# RF.net
KiCad netlist of a schematic drawn in Altium Designer
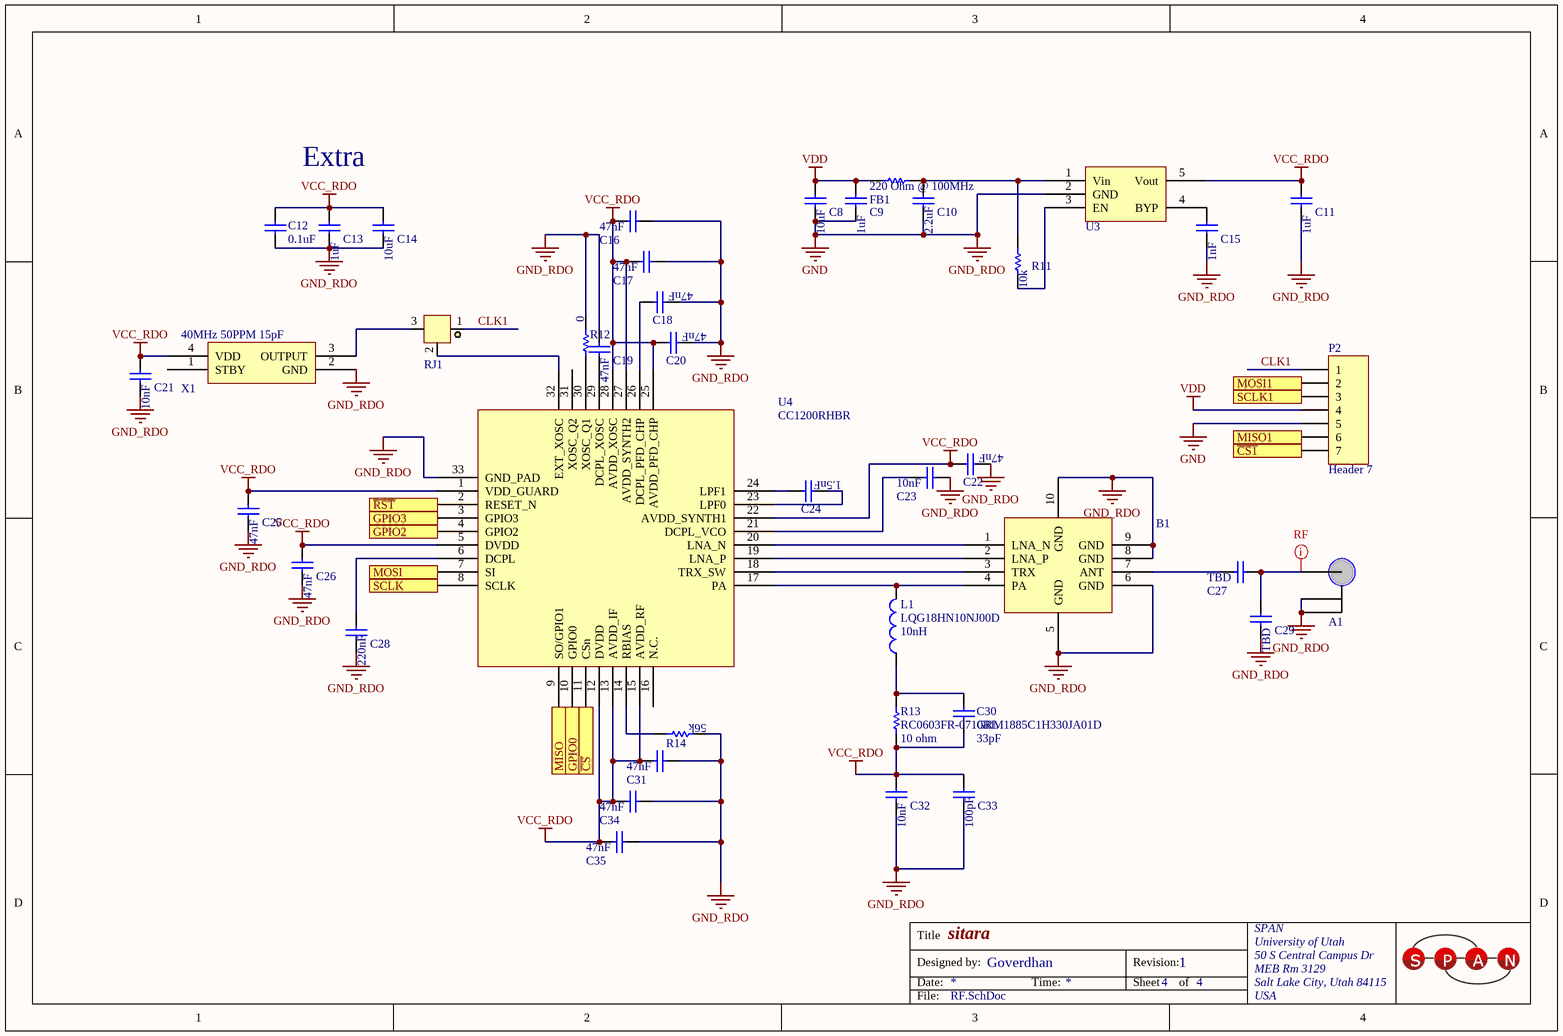
[diagram p0: RF.SchDoc]

(export (version "E")
  (design (tool "Eeschema 10.0.6"))
  (components
    (comp (ref "A1")
      (value "U.FL-R-SMT(01)")
      (footprint "U.FL-R-SMT-1")
      (description "CONN UMC JACK STR 50 OHM SMD")
      (fields (field (name "MANUFACTURER") "Hirose Electric Co Ltd"))
      (libsource (lib "Sara") (part "U.FL-R-SMT(01)"))
    )
    (comp (ref "B1")
      (value "0900PC15J0013")
      (footprint "0900PC15J0013")
      (description "TI CC1120 1121 BALUN FILTER IPC")
      (fields (field (name "MANUFACTURER") "Johanson Technology Inc."))
      (libsource (lib "Sara") (part "0900PC15J0013"))
    )
    (comp (ref "C8")
      (value "GRM188R60J106ME47D")
      (footprint "CAPC1608X08N (0603)")
      (description "CAP CER 10UF 6.3V 20% X5R 0603")
      (fields
        (field (name "MANUFACTURER") "Murata Electronics North America")
        (field (name "TOLERANCE") "±20%")
      )
      (libsource (lib "Sara") (part "GRM188R60J106ME47D"))
    )
    (comp (ref "C9")
      (value "GRM188R61A105KA61D")
      (footprint "CAPC1608X08N (0603)")
      (description "CAP CER 1UF 10V 10% X5R 0603")
      (fields
        (field (name "MANUFACTURER") "Murata Electronics North America")
        (field (name "TOLERANCE") "±10%")
      )
      (libsource (lib "Sara") (part "GRM188R61A105KA61D"))
    )
    (comp (ref "C10")
      (value "GRM188F51A225ZE01D")
      (footprint "CAPC1608X08N (0603)")
      (description "CAP CER 2.2UF 10V Y5V 0603")
      (fields
        (field (name "MANUFACTURER") "Murata Electronics North America")
        (field (name "TOLERANCE") "-20%, +80%")
      )
      (libsource (lib "Sara") (part "GRM188F51A225ZE01D"))
    )
    (comp (ref "C11")
      (value "GRM188R61A105KA61D")
      (footprint "CAPC1608X08N (0603)")
      (description "CAP CER 1UF 10V 10% X5R 0603")
      (fields
        (field (name "MANUFACTURER") "Murata Electronics North America")
        (field (name "TOLERANCE") "±10%")
      )
      (libsource (lib "Sara") (part "GRM188R61A105KA61D"))
    )
    (comp (ref "C12")
      (value "0.1uF")
      (footprint "0603_Cap")
      (description "CAP CER 0.1UF 16V X7R 0603")
      (fields
        (field (name "MANUFACTURER") "AVX Corporation")
        (field (name "MANUFACTURER PART NUMBER") "0603YC104KAT4A")
      )
      (libsource (lib "Sitara") (part "0603YC104KAT4A"))
    )
    (comp (ref "C13")
      (value "GRM188R61A105KA61D")
      (footprint "CAPC1608X08N (0603)")
      (description "CAP CER 1UF 10V 10% X5R 0603")
      (fields
        (field (name "MANUFACTURER") "Murata Electronics North America")
        (field (name "TOLERANCE") "±10%")
      )
      (libsource (lib "Sara") (part "GRM188R61A105KA61D"))
    )
    (comp (ref "C14")
      (value "GRM188R60J106ME47D")
      (footprint "CAPC1608X08N (0603)")
      (description "CAP CER 10UF 6.3V 20% X5R 0603")
      (fields
        (field (name "MANUFACTURER") "Murata Electronics North America")
        (field (name "TOLERANCE") "±20%")
      )
      (libsource (lib "Sara") (part "GRM188R60J106ME47D"))
    )
    (comp (ref "C15")
      (value "GRM1885C1H102JA01D")
      (footprint "CAPC1608X08N (0603)")
      (description "CAP CER 1000PF 50V 5% NP0 0603")
      (fields
        (field (name "MANUFACTURER") "Murata Electronics North America")
        (field (name "TOLERANCE") "±5%")
      )
      (libsource (lib "Sara") (part "GRM1885C1H102JA01D"))
    )
    (comp (ref "C16")
      (value "GCM188R71H473KA55D")
      (footprint "CAPC1608X08N (0603)")
      (description "CAP CER 0.047UF 50V 10% X7R 0603")
      (fields
        (field (name "MANUFACTURER") "Murata Electronics North America")
        (field (name "TOLERANCE") "±10%")
      )
      (libsource (lib "Sara") (part "GCM188R71H473KA55D"))
    )
    (comp (ref "C17")
      (value "GCM188R71H473KA55D")
      (footprint "CAPC1608X08N (0603)")
      (description "CAP CER 0.047UF 50V 10% X7R 0603")
      (fields
        (field (name "MANUFACTURER") "Murata Electronics North America")
        (field (name "TOLERANCE") "±10%")
      )
      (libsource (lib "Sara") (part "GCM188R71H473KA55D"))
    )
    (comp (ref "C18")
      (value "GCM188R71H473KA55D")
      (footprint "CAPC1608X08N (0603)")
      (description "CAP CER 0.047UF 50V 10% X7R 0603")
      (fields
        (field (name "MANUFACTURER") "Murata Electronics North America")
        (field (name "TOLERANCE") "±10%")
      )
      (libsource (lib "Sara") (part "GCM188R71H473KA55D"))
    )
    (comp (ref "C19")
      (value "GCM188R71H473KA55D")
      (footprint "CAPC1608X08N (0603)")
      (description "CAP CER 0.047UF 50V 10% X7R 0603")
      (fields
        (field (name "MANUFACTURER") "Murata Electronics North America")
        (field (name "TOLERANCE") "±10%")
      )
      (libsource (lib "Sara") (part "GCM188R71H473KA55D"))
    )
    (comp (ref "C20")
      (value "GCM188R71H473KA55D")
      (footprint "CAPC1608X08N (0603)")
      (description "CAP CER 0.047UF 50V 10% X7R 0603")
      (fields
        (field (name "MANUFACTURER") "Murata Electronics North America")
        (field (name "TOLERANCE") "±10%")
      )
      (libsource (lib "Sara") (part "GCM188R71H473KA55D"))
    )
    (comp (ref "C21")
      (value "GRM188R71H103MA01D")
      (footprint "CAPC1608X08N (0603)")
      (description "CAP CER 10000PF 50V 20% X7R 0603")
      (fields
        (field (name "MANUFACTURER") "Murata Electronics North America")
        (field (name "TOLERANCE") "±20%")
      )
      (libsource (lib "Sara") (part "GRM188R71H103MA01D"))
    )
    (comp (ref "C22")
      (value "GCM188R71H473KA55D")
      (footprint "CAPC1608X08N (0603)")
      (description "CAP CER 0.047UF 50V 10% X7R 0603")
      (fields
        (field (name "MANUFACTURER") "Murata Electronics North America")
        (field (name "TOLERANCE") "±10%")
      )
      (libsource (lib "Sara") (part "GCM188R71H473KA55D"))
    )
    (comp (ref "C23")
      (value "GRM188R71H103MA01D")
      (footprint "CAPC1608X08N (0603)")
      (description "CAP CER 10000PF 50V 20% X7R 0603")
      (fields
        (field (name "MANUFACTURER") "Murata Electronics North America")
        (field (name "TOLERANCE") "±20%")
      )
      (libsource (lib "Sara") (part "GRM188R71H103MA01D"))
    )
    (comp (ref "C24")
      (value "GRM1885C1H152JA01D")
      (footprint "CAPC1608X08N (0603)")
      (description "CAP CER 1500PF 50V 5% NP0 0603")
      (fields
        (field (name "MANUFACTURER") "Murata Electronics North America")
        (field (name "TOLERANCE") "±5%")
      )
      (libsource (lib "Sara") (part "GRM1885C1H152JA01D"))
    )
    (comp (ref "C25")
      (value "GCM188R71H473KA55D")
      (footprint "CAPC1608X08N (0603)")
      (description "CAP CER 0.047UF 50V 10% X7R 0603")
      (fields
        (field (name "MANUFACTURER") "Murata Electronics North America")
        (field (name "TOLERANCE") "±10%")
      )
      (libsource (lib "Sara") (part "GCM188R71H473KA55D"))
    )
    (comp (ref "C26")
      (value "GCM188R71H473KA55D")
      (footprint "CAPC1608X08N (0603)")
      (description "CAP CER 0.047UF 50V 10% X7R 0603")
      (fields
        (field (name "MANUFACTURER") "Murata Electronics North America")
        (field (name "TOLERANCE") "±10%")
      )
      (libsource (lib "Sara") (part "GCM188R71H473KA55D"))
    )
    (comp (ref "C27")
      (value "C_TBD")
      (footprint "CAPC1608X08N (0603)")
      (libsource (lib "Sara") (part "C_TBD"))
    )
    (comp (ref "C28")
      (value "GRM188R71E224KA88D")
      (footprint "CAPC1608X08N (0603)")
      (description "CAP CER 0.22UF 25V 10% X7R 0603")
      (fields
        (field (name "MANUFACTURER") "Murata Electronics North America")
        (field (name "TOLERANCE") "±10%")
      )
      (libsource (lib "Sara") (part "GRM188R71E224KA88D"))
    )
    (comp (ref "C29")
      (value "C_TBD")
      (footprint "CAPC1608X08N (0603)")
      (libsource (lib "Sara") (part "C_TBD"))
    )
    (comp (ref "C30")
      (value "GRM1885C1H330JA01D")
      (footprint "CAPC1608X08N (0603)")
      (description "CAP CER 33PF 50V NP0 0603")
      (fields
        (field (name "MANUFACTURER") "Murata Electronics North America")
        (field (name "TOLERANCE") "±5%")
        (field (name "ALTIUM_VALUE") "33pF")
      )
      (libsource (lib "Sara") (part "GRM1885C1H330JA01D"))
    )
    (comp (ref "C31")
      (value "GCM188R71H473KA55D")
      (footprint "CAPC1608X08N (0603)")
      (description "CAP CER 0.047UF 50V 10% X7R 0603")
      (fields
        (field (name "MANUFACTURER") "Murata Electronics North America")
        (field (name "TOLERANCE") "±10%")
      )
      (libsource (lib "Sara") (part "GCM188R71H473KA55D"))
    )
    (comp (ref "C32")
      (value "GRM188R71H103MA01D")
      (footprint "CAPC1608X08N (0603)")
      (description "CAP CER 10000PF 50V 20% X7R 0603")
      (fields
        (field (name "MANUFACTURER") "Murata Electronics North America")
        (field (name "TOLERANCE") "±20%")
      )
      (libsource (lib "Sara") (part "GRM188R71H103MA01D"))
    )
    (comp (ref "C33")
      (value "GQM1885C1H101JB01D")
      (footprint "CAPC1608X08N (0603)")
      (description "CAP CER 100PF 50V 5% NP0 0603")
      (fields
        (field (name "MANUFACTURER") "Murata Electronics North America")
        (field (name "TOLERANCE") "±5%")
      )
      (libsource (lib "Sara") (part "GQM1885C1H101JB01D"))
    )
    (comp (ref "C34")
      (value "GCM188R71H473KA55D")
      (footprint "CAPC1608X08N (0603)")
      (description "CAP CER 0.047UF 50V 10% X7R 0603")
      (fields
        (field (name "MANUFACTURER") "Murata Electronics North America")
        (field (name "TOLERANCE") "±10%")
      )
      (libsource (lib "Sara") (part "GCM188R71H473KA55D"))
    )
    (comp (ref "C35")
      (value "GCM188R71H473KA55D")
      (footprint "CAPC1608X08N (0603)")
      (description "CAP CER 0.047UF 50V 10% X7R 0603")
      (fields
        (field (name "MANUFACTURER") "Murata Electronics North America")
        (field (name "TOLERANCE") "±10%")
      )
      (libsource (lib "Sara") (part "GCM188R71H473KA55D"))
    )
    (comp (ref "FB1")
      (value "BLM18BD221SN1D")
      (footprint "RESC1608X06N (0603)")
      (description "FERRITE CHIP 220 OHM 200MA 0603")
      (fields (field (name "MANUFACTURER") "Murata Electronics North America"))
      (libsource (lib "Sara") (part "BLM18BD221SN1D"))
    )
    (comp (ref "L1")
      (value "LQG18HN10NJ00D")
      (footprint "INDC1608X08N")
      (description "FIXED IND 10NH 400MA 300 MOHM")
      (fields
        (field (name "MANUFACTURER") "Murata Electronics North America")
        (field (name "TOLERANCE") "±5%")
        (field (name "ALTIUM_VALUE") "10nH")
      )
      (libsource (lib "Sara") (part "LQG18HN10NJ00D"))
    )
    (comp (ref "P2")
      (value "Header 7")
      (footprint "HDR1X7")
      (description "Header, 7-Pin")
      (fields (field (name "PUBLISHER") "Altium Limited"))
      (libsource (lib "Cerberus") (part "Header 7"))
    )
    (comp (ref "R11")
      (value "RC0603FR-0710KL")
      (footprint "RESC1608X06N (0603)")
      (description "RES 10.0K OHM 1/10W 1% 0603 SMD")
      (fields (field (name "MANUFACTURER") "Yageo") (field (name "TOLERANCE") "±1%"))
      (libsource (lib "Sara") (part "RC0603FR-0710KL"))
    )
    (comp (ref "R12")
      (value "MCR03ERTJ000")
      (footprint "RESC1608X06N (0603)")
      (description "RES 0.0 OHM 1/10W JUMP 0603 SMD")
      (fields (field (name "MANUFACTURER") "Rohm Semiconductor") (field (name "TOLERANCE") "Jumper"))
      (libsource (lib "Sara") (part "MCR03ERTJ000"))
    )
    (comp (ref "R13")
      (value "RC0603FR-0710RL")
      (footprint "RESC1608X06N (0603)")
      (description "RES SMD 10 OHM 1% 1/10W 0603")
      (fields
        (field (name "MANUFACTURER") "Yageo")
        (field (name "TOLERANCE") "±1%")
        (field (name "ALTIUM_VALUE") "10 ohm")
      )
      (libsource (lib "Sara") (part "RC0603FR-0710RL"))
    )
    (comp (ref "R14")
      (value "MCR03ERTJ563")
      (footprint "RESC1608X06N (0603)")
      (description "RES 56K OHM 1/10W 5% 0603 SMD")
      (fields (field (name "MANUFACTURER") "Rohm Semiconductor") (field (name "TOLERANCE") "±5%"))
      (libsource (lib "Sara") (part "MCR03ERTJ563"))
    )
    (comp (ref "RJ1")
      (value "R_J")
      (footprint "RJ")
      (description "Resistor Jumper")
      (libsource (lib "Chronos") (part "R_J"))
    )
    (comp (ref "U3")
      (value "FAN2500S30X")
      (footprint "SOT95P280X145-5N")
      (description "IC REG LDO 3V 0.1A SOT23-5")
      (fields (field (name "MANUFACTURER") "Fairchild Semiconductor"))
      (libsource (lib "Sara") (part "FAN2500S30X"))
    )
    (comp (ref "U4")
      (value "CC1200RHBR")
      (footprint "S-PVQFN-N32")
      (description "IC RF TXRX SNGL-CHIP LP 32-QFN")
      (fields (field (name "MANUFACTURER") "Texas Instruments"))
      (libsource (lib "Sara") (part "CC1200RHBR"))
    )
    (comp (ref "X1")
      (value "ASE-40.000MHZ-L-C-T")
      (footprint "3.2x2.5x1.2mmXTAL")
      (description "OSC XO 40.0000MHZ LVCMOS SMD")
      (fields (field (name "MANUFACTURER") "Abracon LLC"))
      (libsource (lib "Sara") (part "ASE-40.000MHZ-L-C-T"))
    )
  )
  (nets
    (net (code "1") (name "/CLK1") (class "Default")
      (node (ref "P2") (pin "1") (pinfunction "1_1") (pintype "passive"))
      (node (ref "RJ1") (pin "1") (pinfunction "1_1") (pintype "passive"))
    )
    (net (code "2") (name "/GPIO0") (class "Default")
      (node (ref "U4") (pin "10") (pinfunction "GPIO0_10") (pintype "passive"))
    )
    (net (code "3") (name "/GPIO2") (class "Default")
      (node (ref "U4") (pin "4") (pinfunction "GPIO2_4") (pintype "passive"))
    )
    (net (code "4") (name "/GPIO3") (class "Default")
      (node (ref "U4") (pin "3") (pinfunction "GPIO3_3") (pintype "passive"))
    )
    (net (code "5") (name "/MISO") (class "Default")
      (node (ref "U4") (pin "9") (pinfunction "SO/GPIO1_9") (pintype "passive"))
    )
    (net (code "6") (name "/MISO1") (class "Default")
      (node (ref "P2") (pin "6") (pinfunction "6_6") (pintype "passive"))
    )
    (net (code "7") (name "/MOSI") (class "Default")
      (node (ref "U4") (pin "7") (pinfunction "SI_7") (pintype "passive"))
    )
    (net (code "8") (name "/MOSI1") (class "Default")
      (node (ref "P2") (pin "2") (pinfunction "2_2") (pintype "passive"))
    )
    (net (code "9") (name "/SCLK") (class "Default")
      (node (ref "U4") (pin "8") (pinfunction "SCLK_8") (pintype "passive"))
    )
    (net (code "10") (name "/SCLK1") (class "Default")
      (node (ref "P2") (pin "3") (pinfunction "3_3") (pintype "passive"))
    )
    (net (code "11") (name "/~{CS1}") (class "Default")
      (node (ref "P2") (pin "7") (pinfunction "7_7") (pintype "passive"))
    )
    (net (code "12") (name "/~{CS}") (class "Default")
      (node (ref "U4") (pin "11") (pinfunction "CSn_11") (pintype "passive"))
    )
    (net (code "13") (name "/~{RST}") (class "Default")
      (node (ref "U4") (pin "2") (pinfunction "RESET_N_2") (pintype "passive"))
    )
    (net (code "14") (name "GND") (class "Default")
      (node (ref "A1") (pin "2") (pinfunction "2_2") (pintype "passive"))
      (node (ref "A1") (pin "3") (pinfunction "3_3") (pintype "passive"))
      (node (ref "B1") (pin "10") (pinfunction "GND_10") (pintype "passive"))
      (node (ref "B1") (pin "5") (pinfunction "GND_5") (pintype "passive"))
      (node (ref "B1") (pin "6") (pinfunction "GND_6") (pintype "passive"))
      (node (ref "B1") (pin "8") (pinfunction "GND_8") (pintype "passive"))
      (node (ref "B1") (pin "9") (pinfunction "GND_9") (pintype "passive"))
      (node (ref "C10") (pin "1") (pinfunction "1_1") (pintype "passive"))
      (node (ref "C11") (pin "1") (pinfunction "1_1") (pintype "passive"))
      (node (ref "C12") (pin "1") (pinfunction "1_1") (pintype "passive"))
      (node (ref "C13") (pin "1") (pinfunction "1_1") (pintype "passive"))
      (node (ref "C14") (pin "1") (pinfunction "1_1") (pintype "passive"))
      (node (ref "C15") (pin "1") (pinfunction "1_1") (pintype "passive"))
      (node (ref "C16") (pin "2") (pinfunction "2_2") (pintype "passive"))
      (node (ref "C17") (pin "2") (pinfunction "2_2") (pintype "passive"))
      (node (ref "C18") (pin "1") (pinfunction "1_1") (pintype "passive"))
      (node (ref "C19") (pin "2") (pinfunction "2_2") (pintype "passive"))
      (node (ref "C20") (pin "1") (pinfunction "1_1") (pintype "passive"))
      (node (ref "C21") (pin "1") (pinfunction "1_1") (pintype "passive"))
      (node (ref "C22") (pin "1") (pinfunction "1_1") (pintype "passive"))
      (node (ref "C23") (pin "2") (pinfunction "2_2") (pintype "passive"))
      (node (ref "C25") (pin "1") (pinfunction "1_1") (pintype "passive"))
      (node (ref "C26") (pin "1") (pinfunction "1_1") (pintype "passive"))
      (node (ref "C28") (pin "1") (pinfunction "1_1") (pintype "passive"))
      (node (ref "C29") (pin "1") (pinfunction "1_1") (pintype "passive"))
      (node (ref "C31") (pin "2") (pinfunction "2_2") (pintype "passive"))
      (node (ref "C32") (pin "1") (pinfunction "1_1") (pintype "passive"))
      (node (ref "C33") (pin "1") (pinfunction "1_1") (pintype "passive"))
      (node (ref "C34") (pin "2") (pinfunction "2_2") (pintype "passive"))
      (node (ref "C35") (pin "2") (pinfunction "2_2") (pintype "passive"))
      (node (ref "C8") (pin "1") (pinfunction "1_1") (pintype "passive"))
      (node (ref "C9") (pin "1") (pinfunction "1_1") (pintype "passive"))
      (node (ref "P2") (pin "5") (pinfunction "5_5") (pintype "passive"))
      (node (ref "R12") (pin "1") (pinfunction "1_1") (pintype "passive"))
      (node (ref "R14") (pin "1") (pinfunction "1_1") (pintype "passive"))
      (node (ref "U3") (pin "2") (pinfunction "GND_2") (pintype "passive"))
      (node (ref "U4") (pin "33") (pinfunction "GND_PAD_33") (pintype "passive"))
      (node (ref "X1") (pin "2") (pinfunction "GND_2") (pintype "passive"))
    )
    (net (code "15") (name "Net-(A1-Pad1)") (class "Default")
      (node (ref "A1") (pin "1") (pinfunction "1_1") (pintype "passive"))
      (node (ref "C27") (pin "2") (pinfunction "2_2") (pintype "passive"))
      (node (ref "C29") (pin "2") (pinfunction "2_2") (pintype "passive"))
    )
    (net (code "16") (name "Net-(B1-ANT)") (class "Default")
      (node (ref "B1") (pin "7") (pinfunction "ANT_7") (pintype "passive"))
      (node (ref "C27") (pin "1") (pinfunction "1_1") (pintype "passive"))
    )
    (net (code "17") (name "Net-(B1-LNA_N)") (class "Default")
      (node (ref "B1") (pin "1") (pinfunction "LNA_N_1") (pintype "passive"))
      (node (ref "U4") (pin "20") (pinfunction "LNA_N_20") (pintype "passive"))
    )
    (net (code "18") (name "Net-(B1-LNA_P)") (class "Default")
      (node (ref "B1") (pin "2") (pinfunction "LNA_P_2") (pintype "passive"))
      (node (ref "U4") (pin "19") (pinfunction "LNA_P_19") (pintype "passive"))
    )
    (net (code "19") (name "Net-(B1-PA)") (class "Default")
      (node (ref "B1") (pin "4") (pinfunction "PA_4") (pintype "passive"))
      (node (ref "L1") (pin "2") (pinfunction "2_2") (pintype "passive"))
      (node (ref "U4") (pin "17") (pinfunction "PA_17") (pintype "passive"))
    )
    (net (code "20") (name "Net-(B1-TRX)") (class "Default")
      (node (ref "B1") (pin "3") (pinfunction "TRX_3") (pintype "passive"))
      (node (ref "U4") (pin "18") (pinfunction "TRX_SW_18") (pintype "passive"))
    )
    (net (code "21") (name "Net-(C30-Pad2)") (class "Default")
      (node (ref "C30") (pin "2") (pinfunction "2_2") (pintype "passive"))
      (node (ref "L1") (pin "1") (pinfunction "1_1") (pintype "passive"))
      (node (ref "R13") (pin "2") (pinfunction "2_2") (pintype "passive"))
    )
    (net (code "22") (name "Net-(U3-BYP)") (class "Default")
      (node (ref "C15") (pin "2") (pinfunction "2_2") (pintype "passive"))
      (node (ref "U3") (pin "4") (pinfunction "BYP_4") (pintype "passive"))
    )
    (net (code "23") (name "Net-(U3-EN)") (class "Default")
      (node (ref "R11") (pin "1") (pinfunction "1_1") (pintype "passive"))
      (node (ref "U3") (pin "3") (pinfunction "EN_3") (pintype "passive"))
    )
    (net (code "24") (name "Net-(U3-Vin)") (class "Default")
      (node (ref "C10") (pin "2") (pinfunction "2_2") (pintype "passive"))
      (node (ref "FB1") (pin "2") (pinfunction "2_2") (pintype "passive"))
      (node (ref "R11") (pin "2") (pinfunction "2_2") (pintype "passive"))
      (node (ref "U3") (pin "1") (pinfunction "Vin_1") (pintype "passive"))
    )
    (net (code "25") (name "Net-(U4-DCPL)") (class "Default")
      (node (ref "C28") (pin "2") (pinfunction "2_2") (pintype "passive"))
      (node (ref "U4") (pin "6") (pinfunction "DCPL_6") (pintype "passive"))
    )
    (net (code "26") (name "Net-(U4-DCPL_PFD_CHP)") (class "Default")
      (node (ref "C18") (pin "2") (pinfunction "2_2") (pintype "passive"))
      (node (ref "U4") (pin "26") (pinfunction "DCPL_PFD_CHP_26") (pintype "passive"))
    )
    (net (code "27") (name "Net-(U4-DCPL_VCO)") (class "Default")
      (node (ref "C23") (pin "1") (pinfunction "1_1") (pintype "passive"))
      (node (ref "U4") (pin "21") (pinfunction "DCPL_VCO_21") (pintype "passive"))
    )
    (net (code "28") (name "Net-(U4-DCPL_XOSC)") (class "Default")
      (node (ref "C19") (pin "1") (pinfunction "1_1") (pintype "passive"))
      (node (ref "U4") (pin "29") (pinfunction "DCPL_XOSC_29") (pintype "passive"))
    )
    (net (code "29") (name "Net-(U4-EXT_XOSC)") (class "Default")
      (node (ref "RJ1") (pin "2") (pinfunction "2_2") (pintype "passive"))
      (node (ref "U4") (pin "32") (pinfunction "EXT_XOSC_32") (pintype "passive"))
    )
    (net (code "30") (name "Net-(U4-LPF0)") (class "Default")
      (node (ref "C24") (pin "1") (pinfunction "1_1") (pintype "passive"))
      (node (ref "U4") (pin "23") (pinfunction "LPF0_23") (pintype "passive"))
    )
    (net (code "31") (name "Net-(U4-LPF1)") (class "Default")
      (node (ref "C24") (pin "2") (pinfunction "2_2") (pintype "passive"))
      (node (ref "U4") (pin "24") (pinfunction "LPF1_24") (pintype "passive"))
    )
    (net (code "32") (name "Net-(U4-RBIAS)") (class "Default")
      (node (ref "R14") (pin "2") (pinfunction "2_2") (pintype "passive"))
      (node (ref "U4") (pin "14") (pinfunction "RBIAS_14") (pintype "passive"))
    )
    (net (code "33") (name "Net-(U4-XOSC_Q1)") (class "Default")
      (node (ref "R12") (pin "2") (pinfunction "2_2") (pintype "passive"))
      (node (ref "U4") (pin "30") (pinfunction "XOSC_Q1_30") (pintype "passive"))
    )
    (net (code "34") (name "Net-(X1-OUTPUT)") (class "Default")
      (node (ref "RJ1") (pin "3") (pinfunction "3_3") (pintype "passive"))
      (node (ref "X1") (pin "3") (pinfunction "OUTPUT_3") (pintype "passive"))
    )
    (net (code "35") (name "VCC_RDO") (class "Default")
      (node (ref "C11") (pin "2") (pinfunction "2_2") (pintype "passive"))
      (node (ref "C12") (pin "2") (pinfunction "2_2") (pintype "passive"))
      (node (ref "C13") (pin "2") (pinfunction "2_2") (pintype "passive"))
      (node (ref "C14") (pin "2") (pinfunction "2_2") (pintype "passive"))
      (node (ref "C16") (pin "1") (pinfunction "1_1") (pintype "passive"))
      (node (ref "C17") (pin "1") (pinfunction "1_1") (pintype "passive"))
      (node (ref "C20") (pin "2") (pinfunction "2_2") (pintype "passive"))
      (node (ref "C21") (pin "2") (pinfunction "2_2") (pintype "passive"))
      (node (ref "C22") (pin "2") (pinfunction "2_2") (pintype "passive"))
      (node (ref "C25") (pin "2") (pinfunction "2_2") (pintype "passive"))
      (node (ref "C26") (pin "2") (pinfunction "2_2") (pintype "passive"))
      (node (ref "C30") (pin "1") (pinfunction "1_1") (pintype "passive"))
      (node (ref "C31") (pin "1") (pinfunction "1_1") (pintype "passive"))
      (node (ref "C32") (pin "2") (pinfunction "2_2") (pintype "passive"))
      (node (ref "C33") (pin "2") (pinfunction "2_2") (pintype "passive"))
      (node (ref "C34") (pin "1") (pinfunction "1_1") (pintype "passive"))
      (node (ref "C35") (pin "1") (pinfunction "1_1") (pintype "passive"))
      (node (ref "R13") (pin "1") (pinfunction "1_1") (pintype "passive"))
      (node (ref "U3") (pin "5") (pinfunction "Vout_5") (pintype "passive"))
      (node (ref "U4") (pin "1") (pinfunction "VDD_GUARD_1") (pintype "passive"))
      (node (ref "U4") (pin "12") (pinfunction "DVDD_12") (pintype "passive"))
      (node (ref "U4") (pin "13") (pinfunction "AVDD_IF_13") (pintype "passive"))
      (node (ref "U4") (pin "15") (pinfunction "AVDD_RF_15") (pintype "passive"))
      (node (ref "U4") (pin "22") (pinfunction "AVDD_SYNTH1_22") (pintype "passive"))
      (node (ref "U4") (pin "25") (pinfunction "AVDD_PFD_CHP_25") (pintype "passive"))
      (node (ref "U4") (pin "27") (pinfunction "AVDD_SYNTH2_27") (pintype "passive"))
      (node (ref "U4") (pin "28") (pinfunction "AVDD_XOSC_28") (pintype "passive"))
      (node (ref "U4") (pin "5") (pinfunction "DVDD_5") (pintype "passive"))
      (node (ref "X1") (pin "4") (pinfunction "VDD_4") (pintype "passive"))
    )
    (net (code "36") (name "VDD") (class "Default")
      (node (ref "C8") (pin "2") (pinfunction "2_2") (pintype "passive"))
      (node (ref "C9") (pin "2") (pinfunction "2_2") (pintype "passive"))
      (node (ref "FB1") (pin "1") (pinfunction "1_1") (pintype "passive"))
      (node (ref "P2") (pin "4") (pinfunction "4_4") (pintype "passive"))
    )
    (net (code "37") (name "unconnected-(U4-N.C.-Pad16)") (class "Default")
      (node (ref "U4") (pin "16") (pinfunction "N.C._16") (pintype "passive"))
    )
    (net (code "38") (name "unconnected-(U4-XOSC_Q2-Pad31)") (class "Default")
      (node (ref "U4") (pin "31") (pinfunction "XOSC_Q2_31") (pintype "passive"))
    )
    (net (code "39") (name "unconnected-(X1-STBY-Pad1)") (class "Default")
      (node (ref "X1") (pin "1") (pinfunction "STBY_1") (pintype "passive"))
    )
  )
)
